# MCS8951.net
KiCad netlist of a schematic drawn in EAGLE
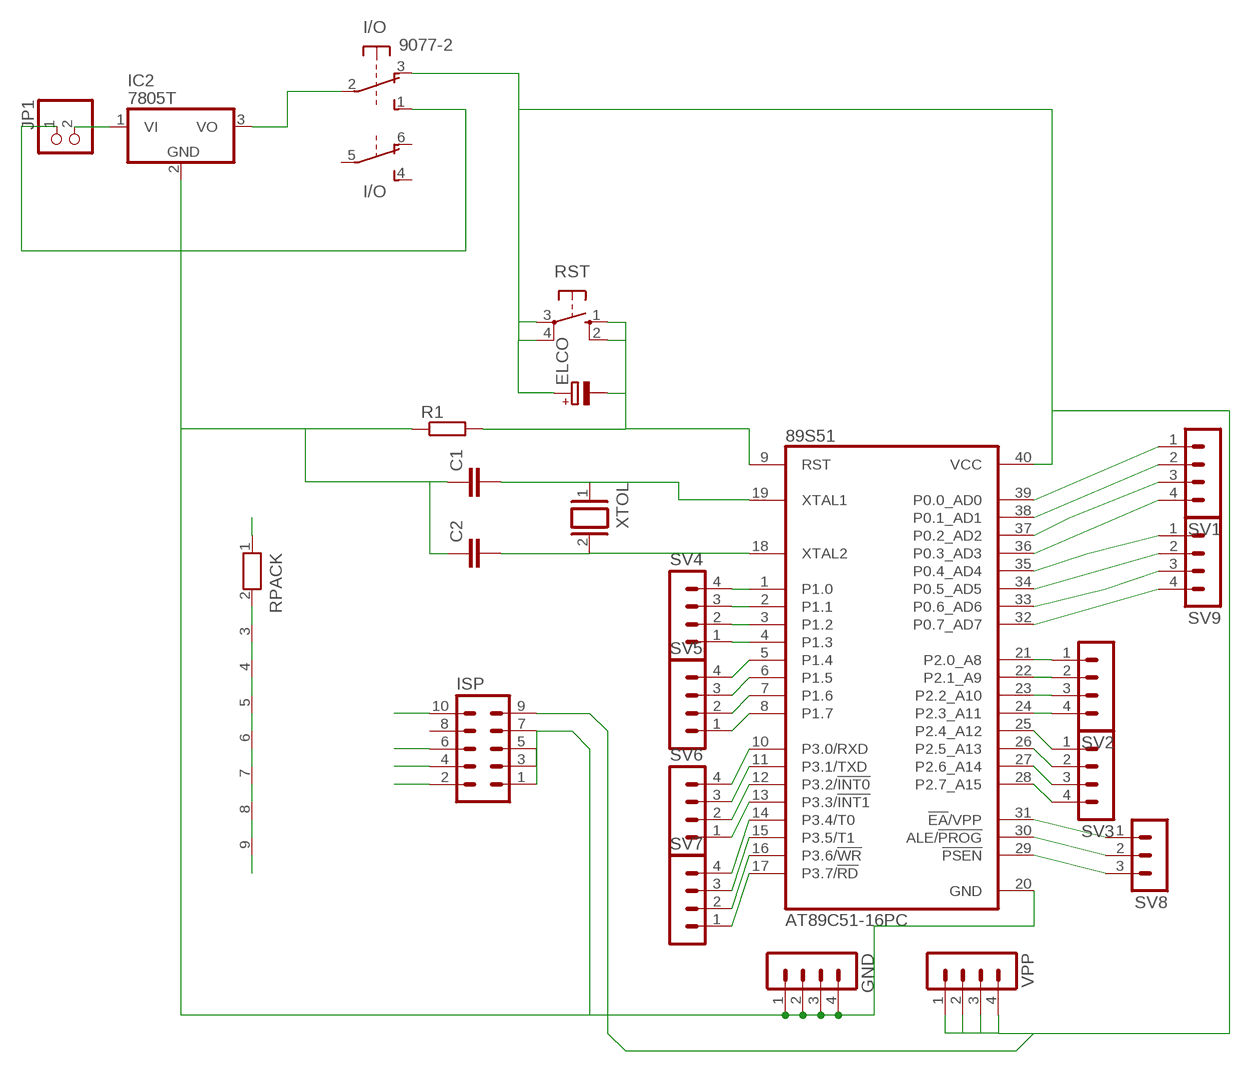
[diagram p0: schematic, sheet 1]

(export (version "E")
  (design (tool "Eeschema 10.0.6"))
  (components
    (comp (ref "89S51")
      (value "AT89C51-16PC")
      (footprint "eagle-import:DIL40")
      (libsource (lib "eagle-import") (part "AT89C51-PC16"))
    )
    (comp (ref "C1")
      (value "C-EU025-030X050")
      (footprint "eagle-import:C025-030X050")
      (libsource (lib "eagle-import") (part "C-EU025-030X050"))
    )
    (comp (ref "C2")
      (value "C-EU025-030X050")
      (footprint "eagle-import:C025-030X050")
      (libsource (lib "eagle-import") (part "C-EU025-030X050"))
    )
    (comp (ref "ELCO")
      (value "CPOL-EUE5-5")
      (footprint "eagle-import:E5-5")
      (libsource (lib "eagle-import") (part "CPOL-EUE5-5"))
    )
    (comp (ref "GND")
      (value "MA04-1")
      (footprint "eagle-import:MA04-1")
      (libsource (lib "eagle-import") (part "MA04-1"))
    )
    (comp (ref "I/O")
      (value "9077-2")
      (footprint "eagle-import:9077-2")
      (libsource (lib "eagle-import") (part "9077-2"))
    )
    (comp (ref "IC2")
      (value "7805T")
      (footprint "eagle-import:TO220H")
      (libsource (lib "eagle-import") (part "78T05"))
    )
    (comp (ref "ISP")
      (value "MA05-2")
      (footprint "eagle-import:MA05-2")
      (libsource (lib "eagle-import") (part "MA05-2"))
    )
    (comp (ref "JP1")
      (value "PINHD-1X2")
      (footprint "eagle-import:1X02")
      (libsource (lib "eagle-import") (part "PINHD-1X2"))
    )
    (comp (ref "R1")
      (value "R-EU_0207/10")
      (footprint "eagle-import:0207_10")
      (libsource (lib "eagle-import") (part "R-EU_0207/10"))
    )
    (comp (ref "RPACK")
      (value "RN08")
      (footprint "eagle-import:RN-9")
      (libsource (lib "eagle-import") (part "RN08"))
    )
    (comp (ref "RST")
      (value "10-XX")
      (footprint "eagle-import:B3F-10XX")
      (fields (field (name "MPN") "B3F-1000"))
      (libsource (lib "eagle-import") (part "10-XX"))
    )
    (comp (ref "SV1")
      (value "MA04-1")
      (footprint "eagle-import:MA04-1")
      (libsource (lib "eagle-import") (part "MA04-1"))
    )
    (comp (ref "SV2")
      (value "MA04-1")
      (footprint "eagle-import:MA04-1")
      (libsource (lib "eagle-import") (part "MA04-1"))
    )
    (comp (ref "SV3")
      (value "MA04-1")
      (footprint "eagle-import:MA04-1")
      (libsource (lib "eagle-import") (part "MA04-1"))
    )
    (comp (ref "SV4")
      (value "MA04-1")
      (footprint "eagle-import:MA04-1")
      (libsource (lib "eagle-import") (part "MA04-1"))
    )
    (comp (ref "SV5")
      (value "MA04-1")
      (footprint "eagle-import:MA04-1")
      (libsource (lib "eagle-import") (part "MA04-1"))
    )
    (comp (ref "SV6")
      (value "MA04-1")
      (footprint "eagle-import:MA04-1")
      (libsource (lib "eagle-import") (part "MA04-1"))
    )
    (comp (ref "SV7")
      (value "MA04-1")
      (footprint "eagle-import:MA04-1")
      (libsource (lib "eagle-import") (part "MA04-1"))
    )
    (comp (ref "SV8")
      (value "MA03-1")
      (footprint "eagle-import:MA03-1")
      (libsource (lib "eagle-import") (part "MA03-1"))
    )
    (comp (ref "SV9")
      (value "MA04-1")
      (footprint "eagle-import:MA04-1")
      (libsource (lib "eagle-import") (part "MA04-1"))
    )
    (comp (ref "VPP")
      (value "MA04-1")
      (footprint "eagle-import:MA04-1")
      (libsource (lib "eagle-import") (part "MA04-1"))
    )
    (comp (ref "XTOL")
      (value "XTAL/S")
      (footprint "eagle-import:QS")
      (libsource (lib "eagle-import") (part "XTAL/S"))
    )
  )
  (nets
    (net (code "1") (name "/MISO") (class "Default")
      (node (ref "89S51") (pin "7") (pinfunction "P1.6_7") (pintype "bidirectional"))
      (node (ref "ISP") (pin "2") (pinfunction "2_2") (pintype "passive"))
      (node (ref "SV5") (pin "2") (pinfunction "2_2") (pintype "passive"))
    )
    (net (code "2") (name "/MOSI") (class "Default")
      (node (ref "89S51") (pin "6") (pinfunction "P1.5_6") (pintype "bidirectional"))
      (node (ref "ISP") (pin "10") (pinfunction "10_10") (pintype "passive"))
      (node (ref "SV5") (pin "3") (pinfunction "3_3") (pintype "passive"))
    )
    (net (code "3") (name "/R1") (class "Default")
      (node (ref "89S51") (pin "39") (pinfunction "P0.0_AD0_39") (pintype "bidirectional"))
      (node (ref "RPACK") (pin "2") (pinfunction "2_2") (pintype "passive"))
      (node (ref "SV1") (pin "1") (pinfunction "1_1") (pintype "passive"))
    )
    (net (code "4") (name "/R2") (class "Default")
      (node (ref "89S51") (pin "38") (pinfunction "P0.1_AD1_38") (pintype "bidirectional"))
      (node (ref "RPACK") (pin "3") (pinfunction "3_3") (pintype "passive"))
      (node (ref "SV1") (pin "2") (pinfunction "2_2") (pintype "passive"))
    )
    (net (code "5") (name "/R3") (class "Default")
      (node (ref "89S51") (pin "37") (pinfunction "P0.2_AD2_37") (pintype "bidirectional"))
      (node (ref "RPACK") (pin "4") (pinfunction "4_4") (pintype "passive"))
      (node (ref "SV1") (pin "3") (pinfunction "3_3") (pintype "passive"))
    )
    (net (code "6") (name "/R4") (class "Default")
      (node (ref "89S51") (pin "36") (pinfunction "P0.3_AD3_36") (pintype "bidirectional"))
      (node (ref "RPACK") (pin "5") (pinfunction "5_5") (pintype "passive"))
      (node (ref "SV1") (pin "4") (pinfunction "4_4") (pintype "passive"))
    )
    (net (code "7") (name "/R5") (class "Default")
      (node (ref "89S51") (pin "35") (pinfunction "P0.4_AD4_35") (pintype "bidirectional"))
      (node (ref "RPACK") (pin "6") (pinfunction "6_6") (pintype "passive"))
      (node (ref "SV9") (pin "1") (pinfunction "1_1") (pintype "passive"))
    )
    (net (code "8") (name "/R6") (class "Default")
      (node (ref "89S51") (pin "34") (pinfunction "P0.5_AD5_34") (pintype "bidirectional"))
      (node (ref "RPACK") (pin "7") (pinfunction "7_7") (pintype "passive"))
      (node (ref "SV9") (pin "2") (pinfunction "2_2") (pintype "passive"))
    )
    (net (code "9") (name "/R7") (class "Default")
      (node (ref "89S51") (pin "33") (pinfunction "P0.6_AD6_33") (pintype "bidirectional"))
      (node (ref "RPACK") (pin "8") (pinfunction "8_8") (pintype "passive"))
      (node (ref "SV9") (pin "3") (pinfunction "3_3") (pintype "passive"))
    )
    (net (code "10") (name "/R8") (class "Default")
      (node (ref "89S51") (pin "32") (pinfunction "P0.7_AD7_32") (pintype "bidirectional"))
      (node (ref "RPACK") (pin "9") (pinfunction "9_9") (pintype "passive"))
      (node (ref "SV9") (pin "4") (pinfunction "4_4") (pintype "passive"))
    )
    (net (code "11") (name "/RST") (class "Default")
      (node (ref "89S51") (pin "9") (pinfunction "RST_9") (pintype "input"))
      (node (ref "ELCO") (pin "-") (pinfunction "-_-") (pintype "passive"))
      (node (ref "ISP") (pin "6") (pinfunction "6_6") (pintype "passive"))
      (node (ref "R1") (pin "2") (pinfunction "2_2") (pintype "passive"))
      (node (ref "RST") (pin "1") (pinfunction "S_1") (pintype "passive"))
      (node (ref "RST") (pin "2") (pinfunction "S1_2") (pintype "passive"))
    )
    (net (code "12") (name "/SCK") (class "Default")
      (node (ref "89S51") (pin "8") (pinfunction "P1.7_8") (pintype "bidirectional"))
      (node (ref "ISP") (pin "4") (pinfunction "4_4") (pintype "passive"))
      (node (ref "SV5") (pin "1") (pinfunction "1_1") (pintype "passive"))
    )
    (net (code "13") (name "/VPP") (class "Default")
      (node (ref "89S51") (pin "40") (pinfunction "VCC_40") (pintype "power_in"))
      (node (ref "ELCO") (pin "+") (pinfunction "+_+") (pintype "passive"))
      (node (ref "I/O") (pin "3") (pinfunction "O_3") (pintype "passive"))
      (node (ref "ISP") (pin "9") (pinfunction "9_9") (pintype "passive"))
      (node (ref "RPACK") (pin "1") (pinfunction "1_1") (pintype "passive"))
      (node (ref "RST") (pin "3") (pinfunction "P_3") (pintype "passive"))
      (node (ref "RST") (pin "4") (pinfunction "P1_4") (pintype "passive"))
      (node (ref "VPP") (pin "1") (pinfunction "1_1") (pintype "passive"))
      (node (ref "VPP") (pin "2") (pinfunction "2_2") (pintype "passive"))
      (node (ref "VPP") (pin "3") (pinfunction "3_3") (pintype "passive"))
      (node (ref "VPP") (pin "4") (pinfunction "4_4") (pintype "passive"))
    )
    (net (code "14") (name "Net-(89S51-ALE{slash}~{PROG})") (class "Default")
      (node (ref "89S51") (pin "30") (pinfunction "ALE/~{PROG}_30") (pintype "output"))
      (node (ref "SV8") (pin "2") (pinfunction "2_2") (pintype "passive"))
    )
    (net (code "15") (name "Net-(89S51-GND)") (class "Default")
      (node (ref "89S51") (pin "20") (pinfunction "GND_20") (pintype "power_in"))
      (node (ref "C1") (pin "1") (pinfunction "1_1") (pintype "passive"))
      (node (ref "C2") (pin "1") (pinfunction "1_1") (pintype "passive"))
      (node (ref "GND") (pin "1") (pinfunction "1_1") (pintype "passive"))
      (node (ref "GND") (pin "2") (pinfunction "2_2") (pintype "passive"))
      (node (ref "GND") (pin "3") (pinfunction "3_3") (pintype "passive"))
      (node (ref "GND") (pin "4") (pinfunction "4_4") (pintype "passive"))
      (node (ref "I/O") (pin "1") (pinfunction "S_1") (pintype "passive"))
      (node (ref "IC2") (pin "2") (pinfunction "GND_2") (pintype "passive"))
      (node (ref "ISP") (pin "1") (pinfunction "1_1") (pintype "passive"))
      (node (ref "ISP") (pin "3") (pinfunction "3_3") (pintype "passive"))
      (node (ref "ISP") (pin "5") (pinfunction "5_5") (pintype "passive"))
      (node (ref "ISP") (pin "7") (pinfunction "7_7") (pintype "passive"))
      (node (ref "JP1") (pin "1") (pinfunction "1_1") (pintype "passive"))
      (node (ref "R1") (pin "1") (pinfunction "1_1") (pintype "passive"))
    )
    (net (code "16") (name "Net-(89S51-P1.0)") (class "Default")
      (node (ref "89S51") (pin "1") (pinfunction "P1.0_1") (pintype "bidirectional"))
      (node (ref "SV4") (pin "4") (pinfunction "4_4") (pintype "passive"))
    )
    (net (code "17") (name "Net-(89S51-P1.1)") (class "Default")
      (node (ref "89S51") (pin "2") (pinfunction "P1.1_2") (pintype "bidirectional"))
      (node (ref "SV4") (pin "3") (pinfunction "3_3") (pintype "passive"))
    )
    (net (code "18") (name "Net-(89S51-P1.2)") (class "Default")
      (node (ref "89S51") (pin "3") (pinfunction "P1.2_3") (pintype "bidirectional"))
      (node (ref "SV4") (pin "2") (pinfunction "2_2") (pintype "passive"))
    )
    (net (code "19") (name "Net-(89S51-P1.3)") (class "Default")
      (node (ref "89S51") (pin "4") (pinfunction "P1.3_4") (pintype "bidirectional"))
      (node (ref "SV4") (pin "1") (pinfunction "1_1") (pintype "passive"))
    )
    (net (code "20") (name "Net-(89S51-P1.4)") (class "Default")
      (node (ref "89S51") (pin "5") (pinfunction "P1.4_5") (pintype "bidirectional"))
      (node (ref "SV5") (pin "4") (pinfunction "4_4") (pintype "passive"))
    )
    (net (code "21") (name "Net-(89S51-P2.0_A8)") (class "Default")
      (node (ref "89S51") (pin "21") (pinfunction "P2.0_A8_21") (pintype "bidirectional"))
      (node (ref "SV2") (pin "1") (pinfunction "1_1") (pintype "passive"))
    )
    (net (code "22") (name "Net-(89S51-P2.1_A9)") (class "Default")
      (node (ref "89S51") (pin "22") (pinfunction "P2.1_A9_22") (pintype "bidirectional"))
      (node (ref "SV2") (pin "2") (pinfunction "2_2") (pintype "passive"))
    )
    (net (code "23") (name "Net-(89S51-P2.2_A10)") (class "Default")
      (node (ref "89S51") (pin "23") (pinfunction "P2.2_A10_23") (pintype "bidirectional"))
      (node (ref "SV2") (pin "3") (pinfunction "3_3") (pintype "passive"))
    )
    (net (code "24") (name "Net-(89S51-P2.3_A11)") (class "Default")
      (node (ref "89S51") (pin "24") (pinfunction "P2.3_A11_24") (pintype "bidirectional"))
      (node (ref "SV2") (pin "4") (pinfunction "4_4") (pintype "passive"))
    )
    (net (code "25") (name "Net-(89S51-P2.4_A12)") (class "Default")
      (node (ref "89S51") (pin "25") (pinfunction "P2.4_A12_25") (pintype "bidirectional"))
      (node (ref "SV3") (pin "1") (pinfunction "1_1") (pintype "passive"))
    )
    (net (code "26") (name "Net-(89S51-P2.5_A13)") (class "Default")
      (node (ref "89S51") (pin "26") (pinfunction "P2.5_A13_26") (pintype "bidirectional"))
      (node (ref "SV3") (pin "2") (pinfunction "2_2") (pintype "passive"))
    )
    (net (code "27") (name "Net-(89S51-P2.6_A14)") (class "Default")
      (node (ref "89S51") (pin "27") (pinfunction "P2.6_A14_27") (pintype "bidirectional"))
      (node (ref "SV3") (pin "3") (pinfunction "3_3") (pintype "passive"))
    )
    (net (code "28") (name "Net-(89S51-P2.7_A15)") (class "Default")
      (node (ref "89S51") (pin "28") (pinfunction "P2.7_A15_28") (pintype "bidirectional"))
      (node (ref "SV3") (pin "4") (pinfunction "4_4") (pintype "passive"))
    )
    (net (code "29") (name "Net-(89S51-P3.0{slash}RXD)") (class "Default")
      (node (ref "89S51") (pin "10") (pinfunction "P3.0/RXD_10") (pintype "bidirectional"))
      (node (ref "SV6") (pin "4") (pinfunction "4_4") (pintype "passive"))
    )
    (net (code "30") (name "Net-(89S51-P3.1{slash}TXD)") (class "Default")
      (node (ref "89S51") (pin "11") (pinfunction "P3.1/TXD_11") (pintype "bidirectional"))
      (node (ref "SV6") (pin "3") (pinfunction "3_3") (pintype "passive"))
    )
    (net (code "31") (name "Net-(89S51-P3.2{slash}~{INT0})") (class "Default")
      (node (ref "89S51") (pin "12") (pinfunction "P3.2/~{INT0}_12") (pintype "bidirectional"))
      (node (ref "SV6") (pin "2") (pinfunction "2_2") (pintype "passive"))
    )
    (net (code "32") (name "Net-(89S51-P3.3{slash}~{INT1})") (class "Default")
      (node (ref "89S51") (pin "13") (pinfunction "P3.3/~{INT1}_13") (pintype "bidirectional"))
      (node (ref "SV6") (pin "1") (pinfunction "1_1") (pintype "passive"))
    )
    (net (code "33") (name "Net-(89S51-P3.4{slash}T0)") (class "Default")
      (node (ref "89S51") (pin "14") (pinfunction "P3.4/T0_14") (pintype "bidirectional"))
      (node (ref "SV7") (pin "4") (pinfunction "4_4") (pintype "passive"))
    )
    (net (code "34") (name "Net-(89S51-P3.5{slash}T1)") (class "Default")
      (node (ref "89S51") (pin "15") (pinfunction "P3.5/T1_15") (pintype "bidirectional"))
      (node (ref "SV7") (pin "3") (pinfunction "3_3") (pintype "passive"))
    )
    (net (code "35") (name "Net-(89S51-P3.6{slash}~{WR})") (class "Default")
      (node (ref "89S51") (pin "16") (pinfunction "P3.6/~{WR}_16") (pintype "bidirectional"))
      (node (ref "SV7") (pin "2") (pinfunction "2_2") (pintype "passive"))
    )
    (net (code "36") (name "Net-(89S51-P3.7{slash}~{RD})") (class "Default")
      (node (ref "89S51") (pin "17") (pinfunction "P3.7/~{RD}_17") (pintype "bidirectional"))
      (node (ref "SV7") (pin "1") (pinfunction "1_1") (pintype "passive"))
    )
    (net (code "37") (name "Net-(89S51-XTAL1)") (class "Default")
      (node (ref "89S51") (pin "19") (pinfunction "XTAL1_19") (pintype "input"))
      (node (ref "C1") (pin "2") (pinfunction "2_2") (pintype "passive"))
      (node (ref "XTOL") (pin "1") (pinfunction "1_1") (pintype "passive"))
    )
    (net (code "38") (name "Net-(89S51-XTAL2)") (class "Default")
      (node (ref "89S51") (pin "18") (pinfunction "XTAL2_18") (pintype "input"))
      (node (ref "C2") (pin "2") (pinfunction "2_2") (pintype "passive"))
      (node (ref "XTOL") (pin "2") (pinfunction "2_2") (pintype "passive"))
    )
    (net (code "39") (name "Net-(89S51-~{EA}{slash}VPP)") (class "Default")
      (node (ref "89S51") (pin "31") (pinfunction "~{EA}/VPP_31") (pintype "input"))
      (node (ref "SV8") (pin "1") (pinfunction "1_1") (pintype "passive"))
    )
    (net (code "40") (name "Net-(89S51-~{PSEN})") (class "Default")
      (node (ref "89S51") (pin "29") (pinfunction "~{PSEN}_29") (pintype "output"))
      (node (ref "SV8") (pin "3") (pinfunction "3_3") (pintype "passive"))
    )
    (net (code "41") (name "Net-(I/OA-P)") (class "Default")
      (node (ref "I/O") (pin "2") (pinfunction "P_2") (pintype "passive"))
      (node (ref "IC2") (pin "3") (pinfunction "VO_3") (pintype "passive"))
    )
    (net (code "42") (name "Net-(IC2-VI)") (class "Default")
      (node (ref "IC2") (pin "1") (pinfunction "VI_1") (pintype "input"))
      (node (ref "JP1") (pin "2") (pinfunction "2_2") (pintype "passive"))
    )
    (net (code "43") (name "unconnected-(I/OB-O-Pad6)") (class "Default")
      (node (ref "I/O") (pin "6") (pinfunction "O_6") (pintype "passive"))
    )
    (net (code "44") (name "unconnected-(I/OB-P-Pad5)") (class "Default")
      (node (ref "I/O") (pin "5") (pinfunction "P_5") (pintype "passive"))
    )
    (net (code "45") (name "unconnected-(I/OB-S-Pad4)") (class "Default")
      (node (ref "I/O") (pin "4") (pinfunction "S_4") (pintype "passive"))
    )
    (net (code "46") (name "unconnected-(ISP-Pad8)") (class "Default")
      (node (ref "ISP") (pin "8") (pinfunction "8_8") (pintype "passive"))
    )
  )
)
